# Gyro_SinarX.net
KiCad netlist of a schematic drawn in EAGLE
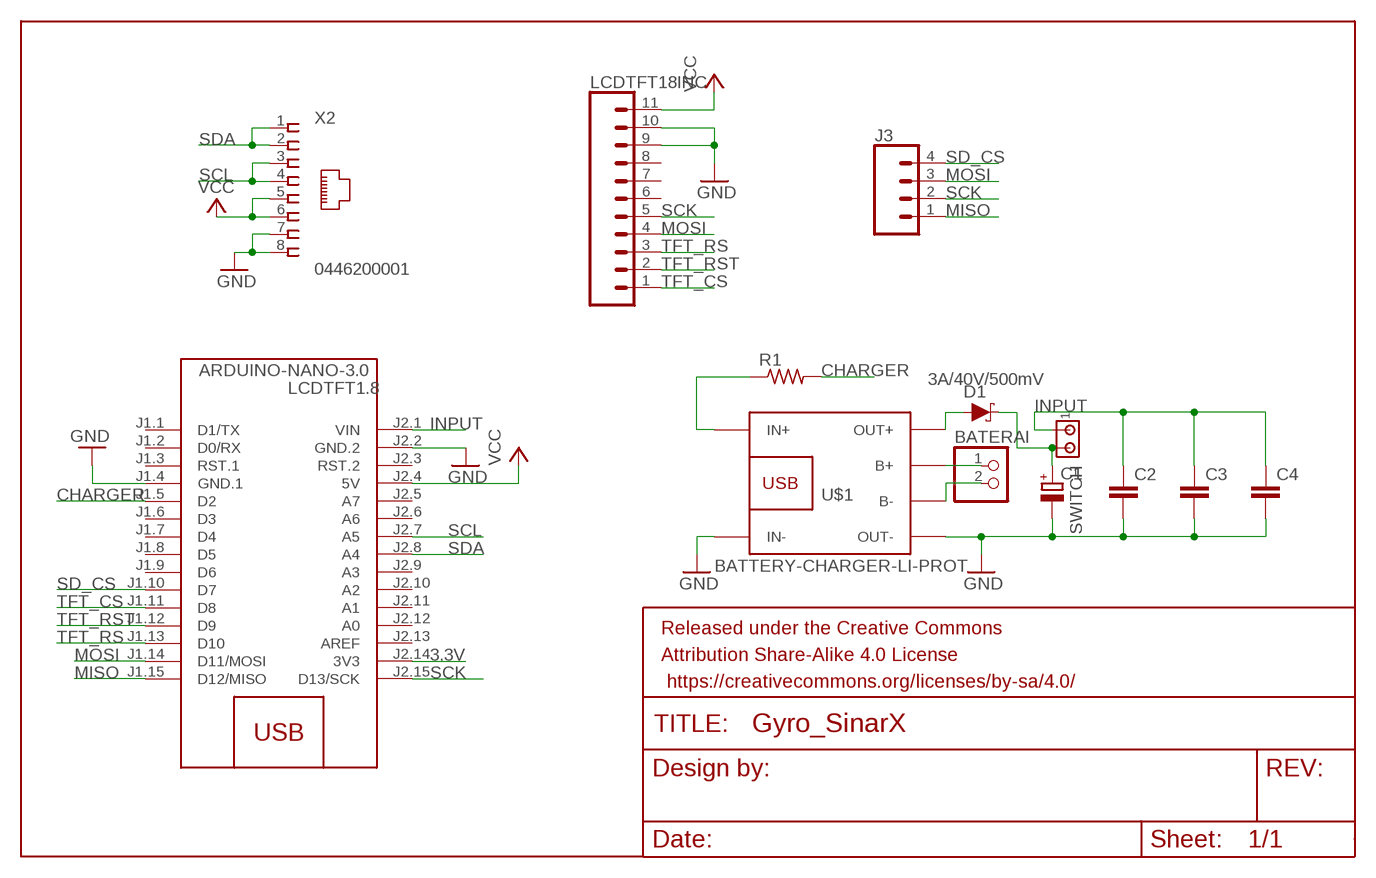
[diagram p0: schematic, sheet 1]

(export (version "E")
  (design (tool "Eeschema 10.0.6"))
  (components
    (comp (ref "BATERAI")
      (value "PINHD-1X2/90")
      (footprint "eagle-import:1X02_90")
      (libsource (lib "eagle-import") (part "PINHD-1X2/90"))
    )
    (comp (ref "C1")
      (value "CPOL-EUE2.5-7")
      (footprint "eagle-import:E2,5-7")
      (libsource (lib "eagle-import") (part "CPOL-EUE2.5-7"))
    )
    (comp (ref "C2")
      (value "C-EUC0805K")
      (footprint "eagle-import:C0805K")
      (libsource (lib "eagle-import") (part "C-EUC0805K"))
    )
    (comp (ref "C3")
      (value "C-EUC0805K")
      (footprint "eagle-import:C0805K")
      (libsource (lib "eagle-import") (part "C-EUC0805K"))
    )
    (comp (ref "C4")
      (value "C-EUC0805K")
      (footprint "eagle-import:C0805K")
      (libsource (lib "eagle-import") (part "C-EUC0805K"))
    )
    (comp (ref "D1")
      (value "3A/40V/500mV")
      (footprint "eagle-import:SMA-DIODE")
      (libsource (lib "eagle-import") (part "DIODE-SCHOTTKY-B340A"))
    )
    (comp (ref "FRAME1")
      (value "FRAME-LEDGER")
      (footprint "eagle-import:CREATIVE_COMMONS")
      (libsource (lib "eagle-import") (part "FRAME-LEDGER"))
    )
    (comp (ref "J3")
      (value "CONN_04PTH")
      (footprint "eagle-import:1X04")
      (libsource (lib "eagle-import") (part "CONN_04PTH"))
    )
    (comp (ref "LCDTFT1.8")
      (value "ARDUINO-NANO-3.0")
      (footprint "eagle-import:ARDUINO-NANO-3.0")
      (libsource (lib "eagle-import") (part "ARDUINO-NANO-3.0"))
    )
    (comp (ref "LCDTFT18INC")
      (value "CONN_11")
      (footprint "eagle-import:1X11")
      (libsource (lib "eagle-import") (part "CONN_11"))
    )
    (comp (ref "R1")
      (value "R-US_0207/10")
      (footprint "eagle-import:0207_10")
      (libsource (lib "eagle-import") (part "R-US_0207/10"))
    )
    (comp (ref "SWITCH")
      (value "MTA02-100")
      (footprint "eagle-import:10X02MTA")
      (libsource (lib "eagle-import") (part "MTA02-100"))
    )
    (comp (ref "U$1")
      (value "BATTERY-CHARGER-LI-PROT")
      (footprint "eagle-import:BATTERY-CHARGER-LI-PROT")
      (libsource (lib "eagle-import") (part "BATTERY-CHARGER-LI-PROT"))
    )
    (comp (ref "X2")
      (value "0446200001")
      (footprint "eagle-import:0446200001")
      (fields (field (name "MF") "MOLEX"))
      (libsource (lib "eagle-import") (part "0446200001"))
    )
  )
  (nets
    (net (code "1") (name "/3.3V") (class "Default")
      (node (ref "LCDTFT1.8") (pin "J2.14") (pinfunction "3V3_J2.14") (pintype "power_in"))
    )
    (net (code "2") (name "/CHARGER") (class "Default")
      (node (ref "LCDTFT1.8") (pin "J1.5") (pinfunction "D2_J1.5") (pintype "bidirectional"))
      (node (ref "R1") (pin "2") (pinfunction "2_2") (pintype "passive"))
    )
    (net (code "3") (name "/INPUT") (class "Default")
      (node (ref "C2") (pin "1") (pinfunction "1_1") (pintype "passive"))
      (node (ref "C3") (pin "1") (pinfunction "1_1") (pintype "passive"))
      (node (ref "C4") (pin "1") (pinfunction "1_1") (pintype "passive"))
      (node (ref "LCDTFT1.8") (pin "J2.1") (pinfunction "VIN_J2.1") (pintype "power_in"))
      (node (ref "SWITCH") (pin "1") (pinfunction "1_1") (pintype "passive"))
    )
    (net (code "4") (name "/MISO") (class "Default")
      (node (ref "J3") (pin "1") (pinfunction "1_1") (pintype "passive"))
      (node (ref "LCDTFT1.8") (pin "J1.15") (pinfunction "D12/MISO_J1.15") (pintype "bidirectional"))
    )
    (net (code "5") (name "/MOSI") (class "Default")
      (node (ref "J3") (pin "3") (pinfunction "3_3") (pintype "passive"))
      (node (ref "LCDTFT1.8") (pin "J1.14") (pinfunction "D11/MOSI_J1.14") (pintype "bidirectional"))
      (node (ref "LCDTFT18INC") (pin "4") (pinfunction "4_4") (pintype "passive"))
    )
    (net (code "6") (name "/SCK") (class "Default")
      (node (ref "J3") (pin "2") (pinfunction "2_2") (pintype "passive"))
      (node (ref "LCDTFT1.8") (pin "J2.15") (pinfunction "D13/SCK_J2.15") (pintype "bidirectional"))
      (node (ref "LCDTFT18INC") (pin "5") (pinfunction "5_5") (pintype "passive"))
    )
    (net (code "7") (name "/SCL") (class "Default")
      (node (ref "LCDTFT1.8") (pin "J2.7") (pinfunction "A5_J2.7") (pintype "bidirectional"))
      (node (ref "X2") (pin "3") (pinfunction "3_3") (pintype "passive"))
      (node (ref "X2") (pin "4") (pinfunction "4_4") (pintype "passive"))
    )
    (net (code "8") (name "/SDA") (class "Default")
      (node (ref "LCDTFT1.8") (pin "J2.8") (pinfunction "A4_J2.8") (pintype "bidirectional"))
      (node (ref "X2") (pin "1") (pinfunction "1_1") (pintype "passive"))
      (node (ref "X2") (pin "2") (pinfunction "2_2") (pintype "passive"))
    )
    (net (code "9") (name "/SD_CS") (class "Default")
      (node (ref "J3") (pin "4") (pinfunction "4_4") (pintype "passive"))
      (node (ref "LCDTFT1.8") (pin "J1.10") (pinfunction "D7_J1.10") (pintype "bidirectional"))
    )
    (net (code "10") (name "/TFT_CS") (class "Default")
      (node (ref "LCDTFT1.8") (pin "J1.11") (pinfunction "D8_J1.11") (pintype "bidirectional"))
      (node (ref "LCDTFT18INC") (pin "1") (pinfunction "1_1") (pintype "passive"))
    )
    (net (code "11") (name "/TFT_RS") (class "Default")
      (node (ref "LCDTFT1.8") (pin "J1.13") (pinfunction "D10_J1.13") (pintype "bidirectional"))
      (node (ref "LCDTFT18INC") (pin "3") (pinfunction "3_3") (pintype "passive"))
    )
    (net (code "12") (name "/TFT_RST") (class "Default")
      (node (ref "LCDTFT1.8") (pin "J1.12") (pinfunction "D9_J1.12") (pintype "bidirectional"))
      (node (ref "LCDTFT18INC") (pin "2") (pinfunction "2_2") (pintype "passive"))
    )
    (net (code "13") (name "GND") (class "Default")
      (node (ref "C1") (pin "-") (pinfunction "-_-") (pintype "passive"))
      (node (ref "C2") (pin "2") (pinfunction "2_2") (pintype "passive"))
      (node (ref "C3") (pin "2") (pinfunction "2_2") (pintype "passive"))
      (node (ref "C4") (pin "2") (pinfunction "2_2") (pintype "passive"))
      (node (ref "LCDTFT1.8") (pin "J1.4") (pinfunction "GND.1_J1.4") (pintype "power_in"))
      (node (ref "LCDTFT1.8") (pin "J2.2") (pinfunction "GND.2_J2.2") (pintype "power_in"))
      (node (ref "LCDTFT18INC") (pin "10") (pinfunction "10_10") (pintype "passive"))
      (node (ref "LCDTFT18INC") (pin "9") (pinfunction "9_9") (pintype "passive"))
      (node (ref "U$1") (pin "IN-") (pinfunction "IN-_IN-") (pintype "bidirectional"))
      (node (ref "U$1") (pin "OUT-") (pinfunction "OUT-_OUT-") (pintype "bidirectional"))
      (node (ref "X2") (pin "7") (pinfunction "7_7") (pintype "passive"))
      (node (ref "X2") (pin "8") (pinfunction "8_8") (pintype "passive"))
    )
    (net (code "14") (name "Net-(BATERAI-Pad1)") (class "Default")
      (node (ref "BATERAI") (pin "1") (pinfunction "1_1") (pintype "passive"))
      (node (ref "U$1") (pin "B+") (pinfunction "B+_B+") (pintype "bidirectional"))
    )
    (net (code "15") (name "Net-(BATERAI-Pad2)") (class "Default")
      (node (ref "BATERAI") (pin "2") (pinfunction "2_2") (pintype "passive"))
      (node (ref "U$1") (pin "B-") (pinfunction "B-_B-") (pintype "bidirectional"))
    )
    (net (code "16") (name "Net-(C1-Pad+)") (class "Default")
      (node (ref "C1") (pin "+") (pinfunction "+_+") (pintype "passive"))
      (node (ref "D1") (pin "C") (pinfunction "C_C") (pintype "passive"))
      (node (ref "SWITCH") (pin "2") (pinfunction "2_2") (pintype "passive"))
    )
    (net (code "17") (name "Net-(D1-PadA)") (class "Default")
      (node (ref "D1") (pin "A") (pinfunction "A_A") (pintype "passive"))
      (node (ref "U$1") (pin "OUT+") (pinfunction "OUT+_OUT+") (pintype "bidirectional"))
    )
    (net (code "18") (name "Net-(R1-Pad1)") (class "Default")
      (node (ref "R1") (pin "1") (pinfunction "1_1") (pintype "passive"))
      (node (ref "U$1") (pin "IN+") (pinfunction "IN+_IN+") (pintype "bidirectional"))
    )
    (net (code "19") (name "VCC") (class "Default")
      (node (ref "LCDTFT1.8") (pin "J2.4") (pinfunction "5V_J2.4") (pintype "power_in"))
      (node (ref "LCDTFT18INC") (pin "11") (pinfunction "11_11") (pintype "passive"))
      (node (ref "X2") (pin "5") (pinfunction "5_5") (pintype "passive"))
      (node (ref "X2") (pin "6") (pinfunction "6_6") (pintype "passive"))
    )
    (net (code "20") (name "unconnected-(LCDTFT1.8-A0-PadJ2.12)") (class "Default")
      (node (ref "LCDTFT1.8") (pin "J2.12") (pinfunction "A0_J2.12") (pintype "bidirectional"))
    )
    (net (code "21") (name "unconnected-(LCDTFT1.8-A1-PadJ2.11)") (class "Default")
      (node (ref "LCDTFT1.8") (pin "J2.11") (pinfunction "A1_J2.11") (pintype "bidirectional"))
    )
    (net (code "22") (name "unconnected-(LCDTFT1.8-A2-PadJ2.10)") (class "Default")
      (node (ref "LCDTFT1.8") (pin "J2.10") (pinfunction "A2_J2.10") (pintype "bidirectional"))
    )
    (net (code "23") (name "unconnected-(LCDTFT1.8-A3-PadJ2.9)") (class "Default")
      (node (ref "LCDTFT1.8") (pin "J2.9") (pinfunction "A3_J2.9") (pintype "bidirectional"))
    )
    (net (code "24") (name "unconnected-(LCDTFT1.8-A6-PadJ2.6)") (class "Default")
      (node (ref "LCDTFT1.8") (pin "J2.6") (pinfunction "A6_J2.6") (pintype "bidirectional"))
    )
    (net (code "25") (name "unconnected-(LCDTFT1.8-A7-PadJ2.5)") (class "Default")
      (node (ref "LCDTFT1.8") (pin "J2.5") (pinfunction "A7_J2.5") (pintype "bidirectional"))
    )
    (net (code "26") (name "unconnected-(LCDTFT1.8-AREF-PadJ2.13)") (class "Default")
      (node (ref "LCDTFT1.8") (pin "J2.13") (pinfunction "AREF_J2.13") (pintype "bidirectional"))
    )
    (net (code "27") (name "unconnected-(LCDTFT1.8-D0{slash}RX-PadJ1.2)") (class "Default")
      (node (ref "LCDTFT1.8") (pin "J1.2") (pinfunction "D0/RX_J1.2") (pintype "bidirectional"))
    )
    (net (code "28") (name "unconnected-(LCDTFT1.8-D1{slash}TX-PadJ1.1)") (class "Default")
      (node (ref "LCDTFT1.8") (pin "J1.1") (pinfunction "D1/TX_J1.1") (pintype "bidirectional"))
    )
    (net (code "29") (name "unconnected-(LCDTFT1.8-D3-PadJ1.6)") (class "Default")
      (node (ref "LCDTFT1.8") (pin "J1.6") (pinfunction "D3_J1.6") (pintype "bidirectional"))
    )
    (net (code "30") (name "unconnected-(LCDTFT1.8-D4-PadJ1.7)") (class "Default")
      (node (ref "LCDTFT1.8") (pin "J1.7") (pinfunction "D4_J1.7") (pintype "bidirectional"))
    )
    (net (code "31") (name "unconnected-(LCDTFT1.8-D5-PadJ1.8)") (class "Default")
      (node (ref "LCDTFT1.8") (pin "J1.8") (pinfunction "D5_J1.8") (pintype "bidirectional"))
    )
    (net (code "32") (name "unconnected-(LCDTFT1.8-D6-PadJ1.9)") (class "Default")
      (node (ref "LCDTFT1.8") (pin "J1.9") (pinfunction "D6_J1.9") (pintype "bidirectional"))
    )
    (net (code "33") (name "unconnected-(LCDTFT1.8-RST.1-PadJ1.3)") (class "Default")
      (node (ref "LCDTFT1.8") (pin "J1.3") (pinfunction "RST.1_J1.3") (pintype "bidirectional"))
    )
    (net (code "34") (name "unconnected-(LCDTFT1.8-RST.2-PadJ2.3)") (class "Default")
      (node (ref "LCDTFT1.8") (pin "J2.3") (pinfunction "RST.2_J2.3") (pintype "bidirectional"))
    )
    (net (code "35") (name "unconnected-(LCDTFT18INC-Pad6)") (class "Default")
      (node (ref "LCDTFT18INC") (pin "6") (pinfunction "6_6") (pintype "passive"))
    )
    (net (code "36") (name "unconnected-(LCDTFT18INC-Pad7)") (class "Default")
      (node (ref "LCDTFT18INC") (pin "7") (pinfunction "7_7") (pintype "passive"))
    )
    (net (code "37") (name "unconnected-(LCDTFT18INC-Pad8)") (class "Default")
      (node (ref "LCDTFT18INC") (pin "8") (pinfunction "8_8") (pintype "passive"))
    )
  )
)
